# ProDoc_ESP32_V2_Interface_Board_Abed_202.net
KiCad netlist of a schematic drawn in EasyEDA Pro
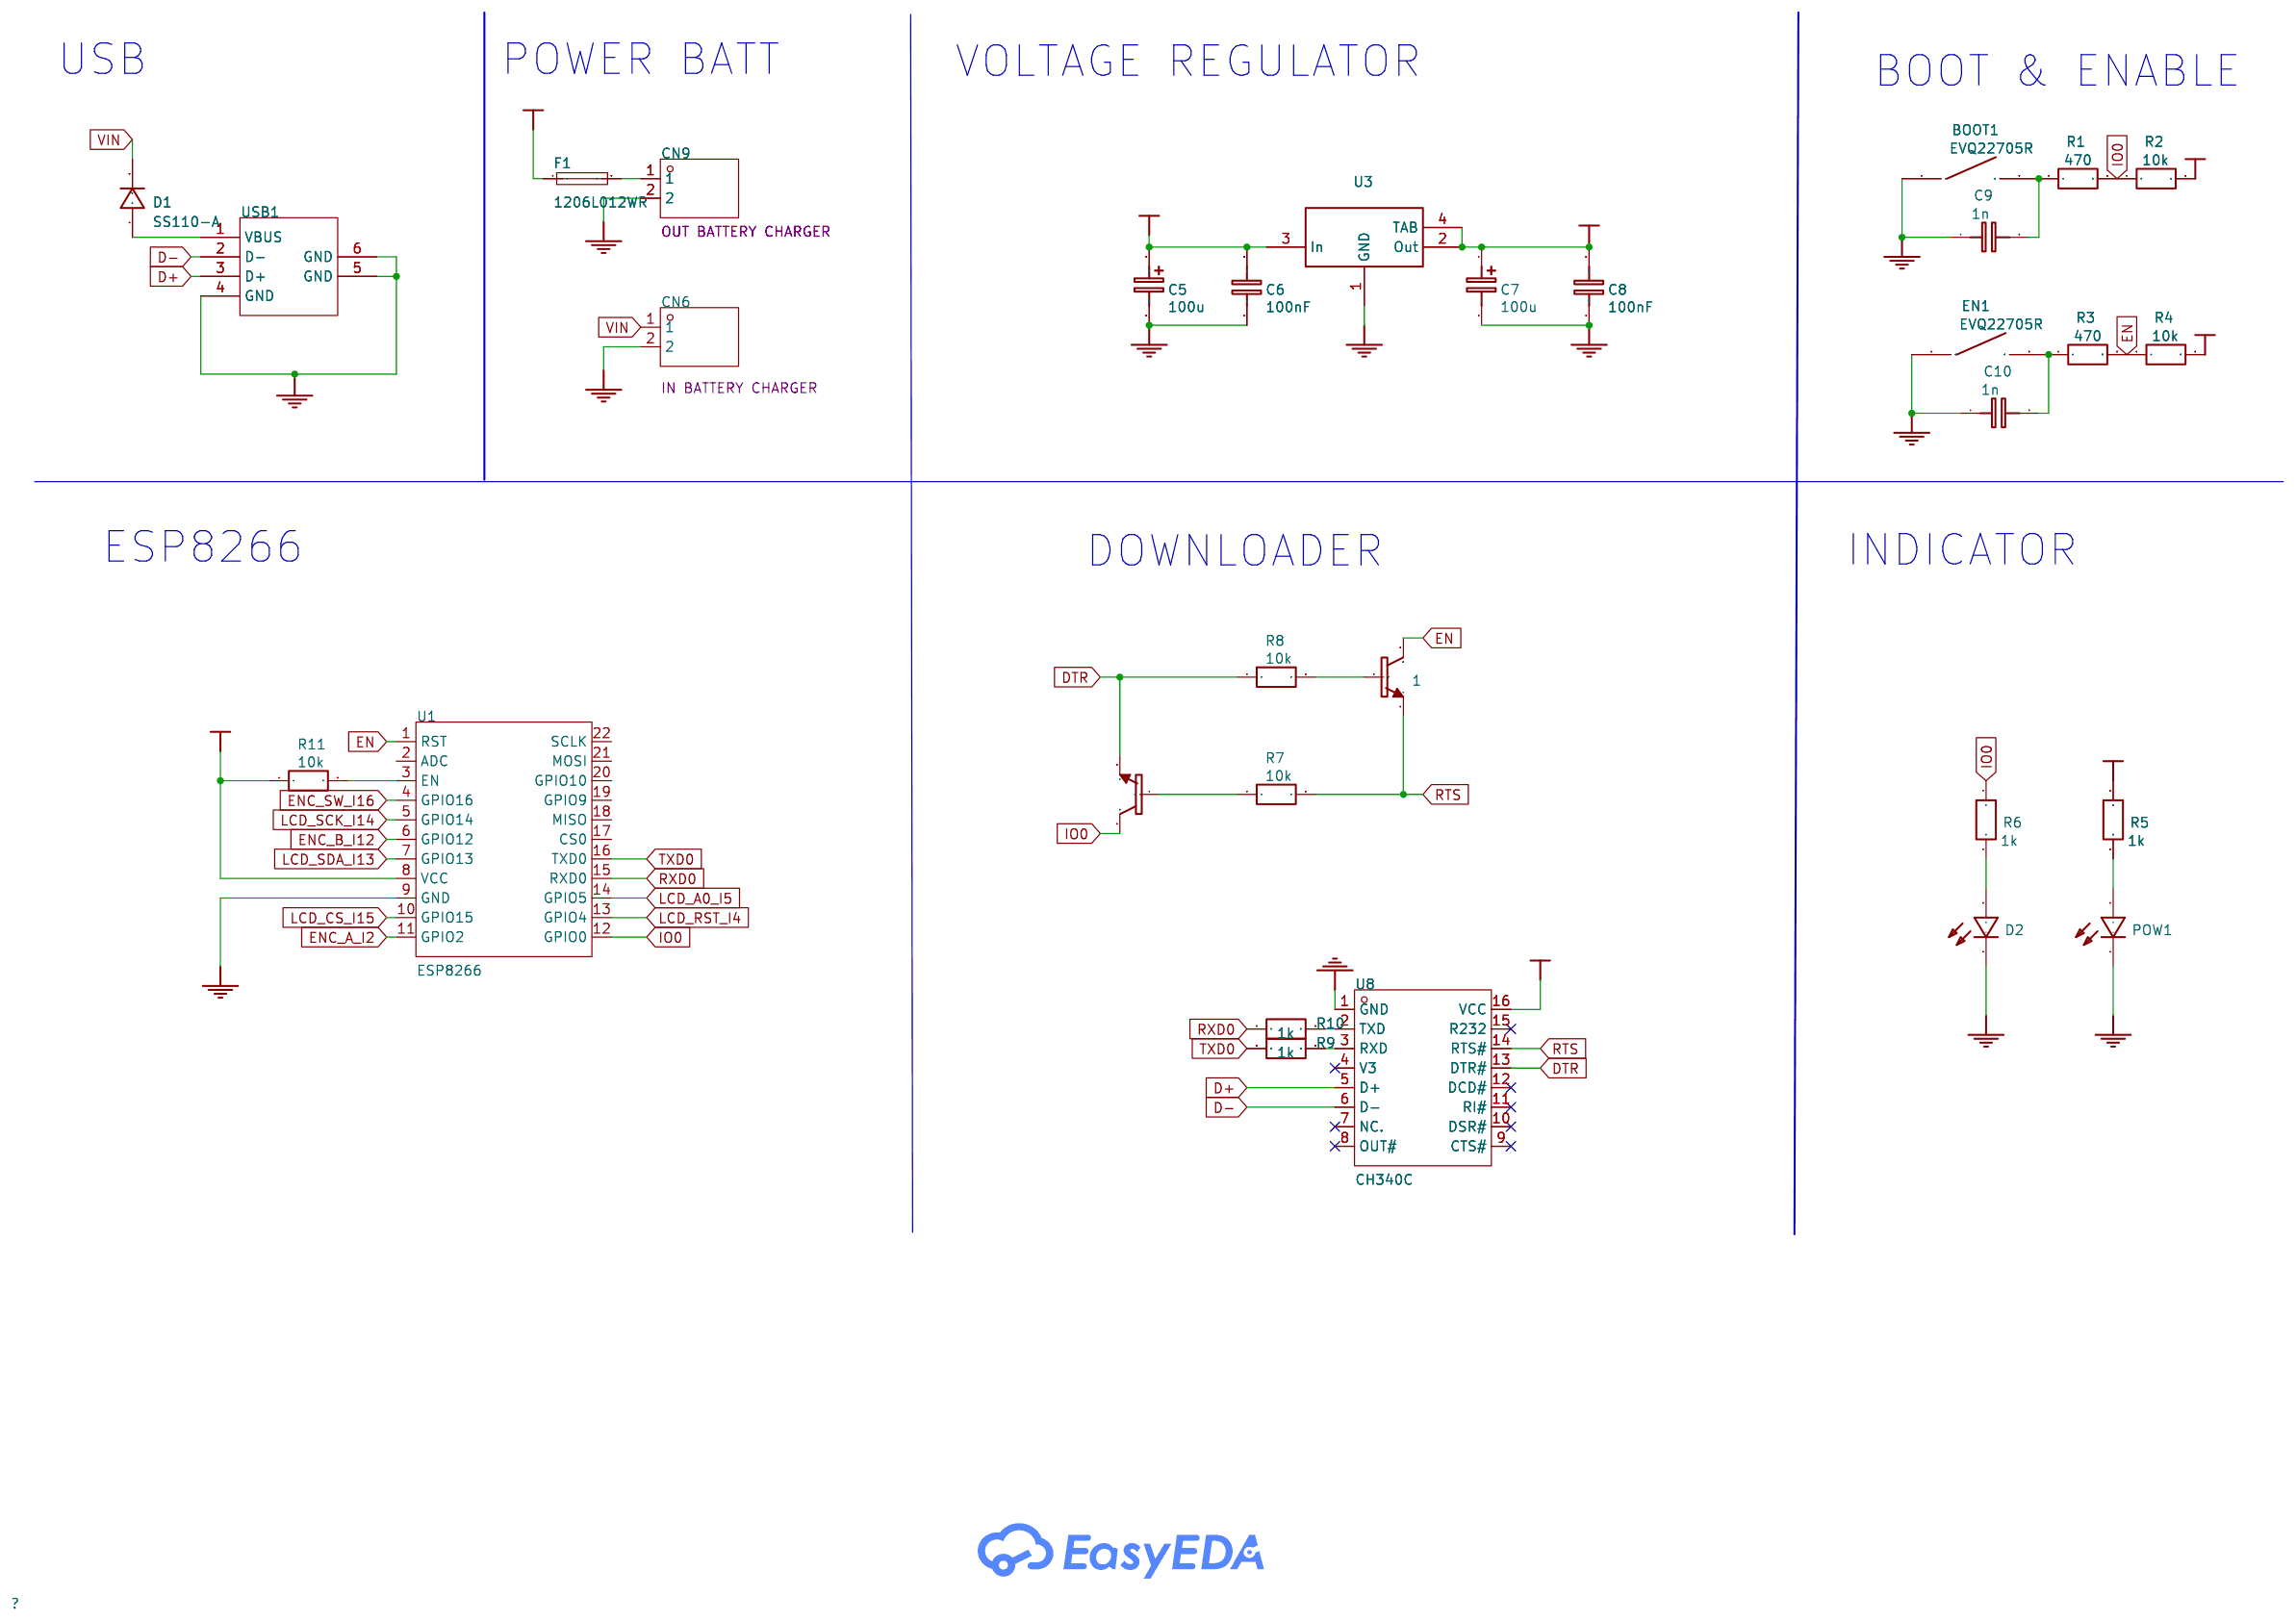
[diagram p0: Minsys]
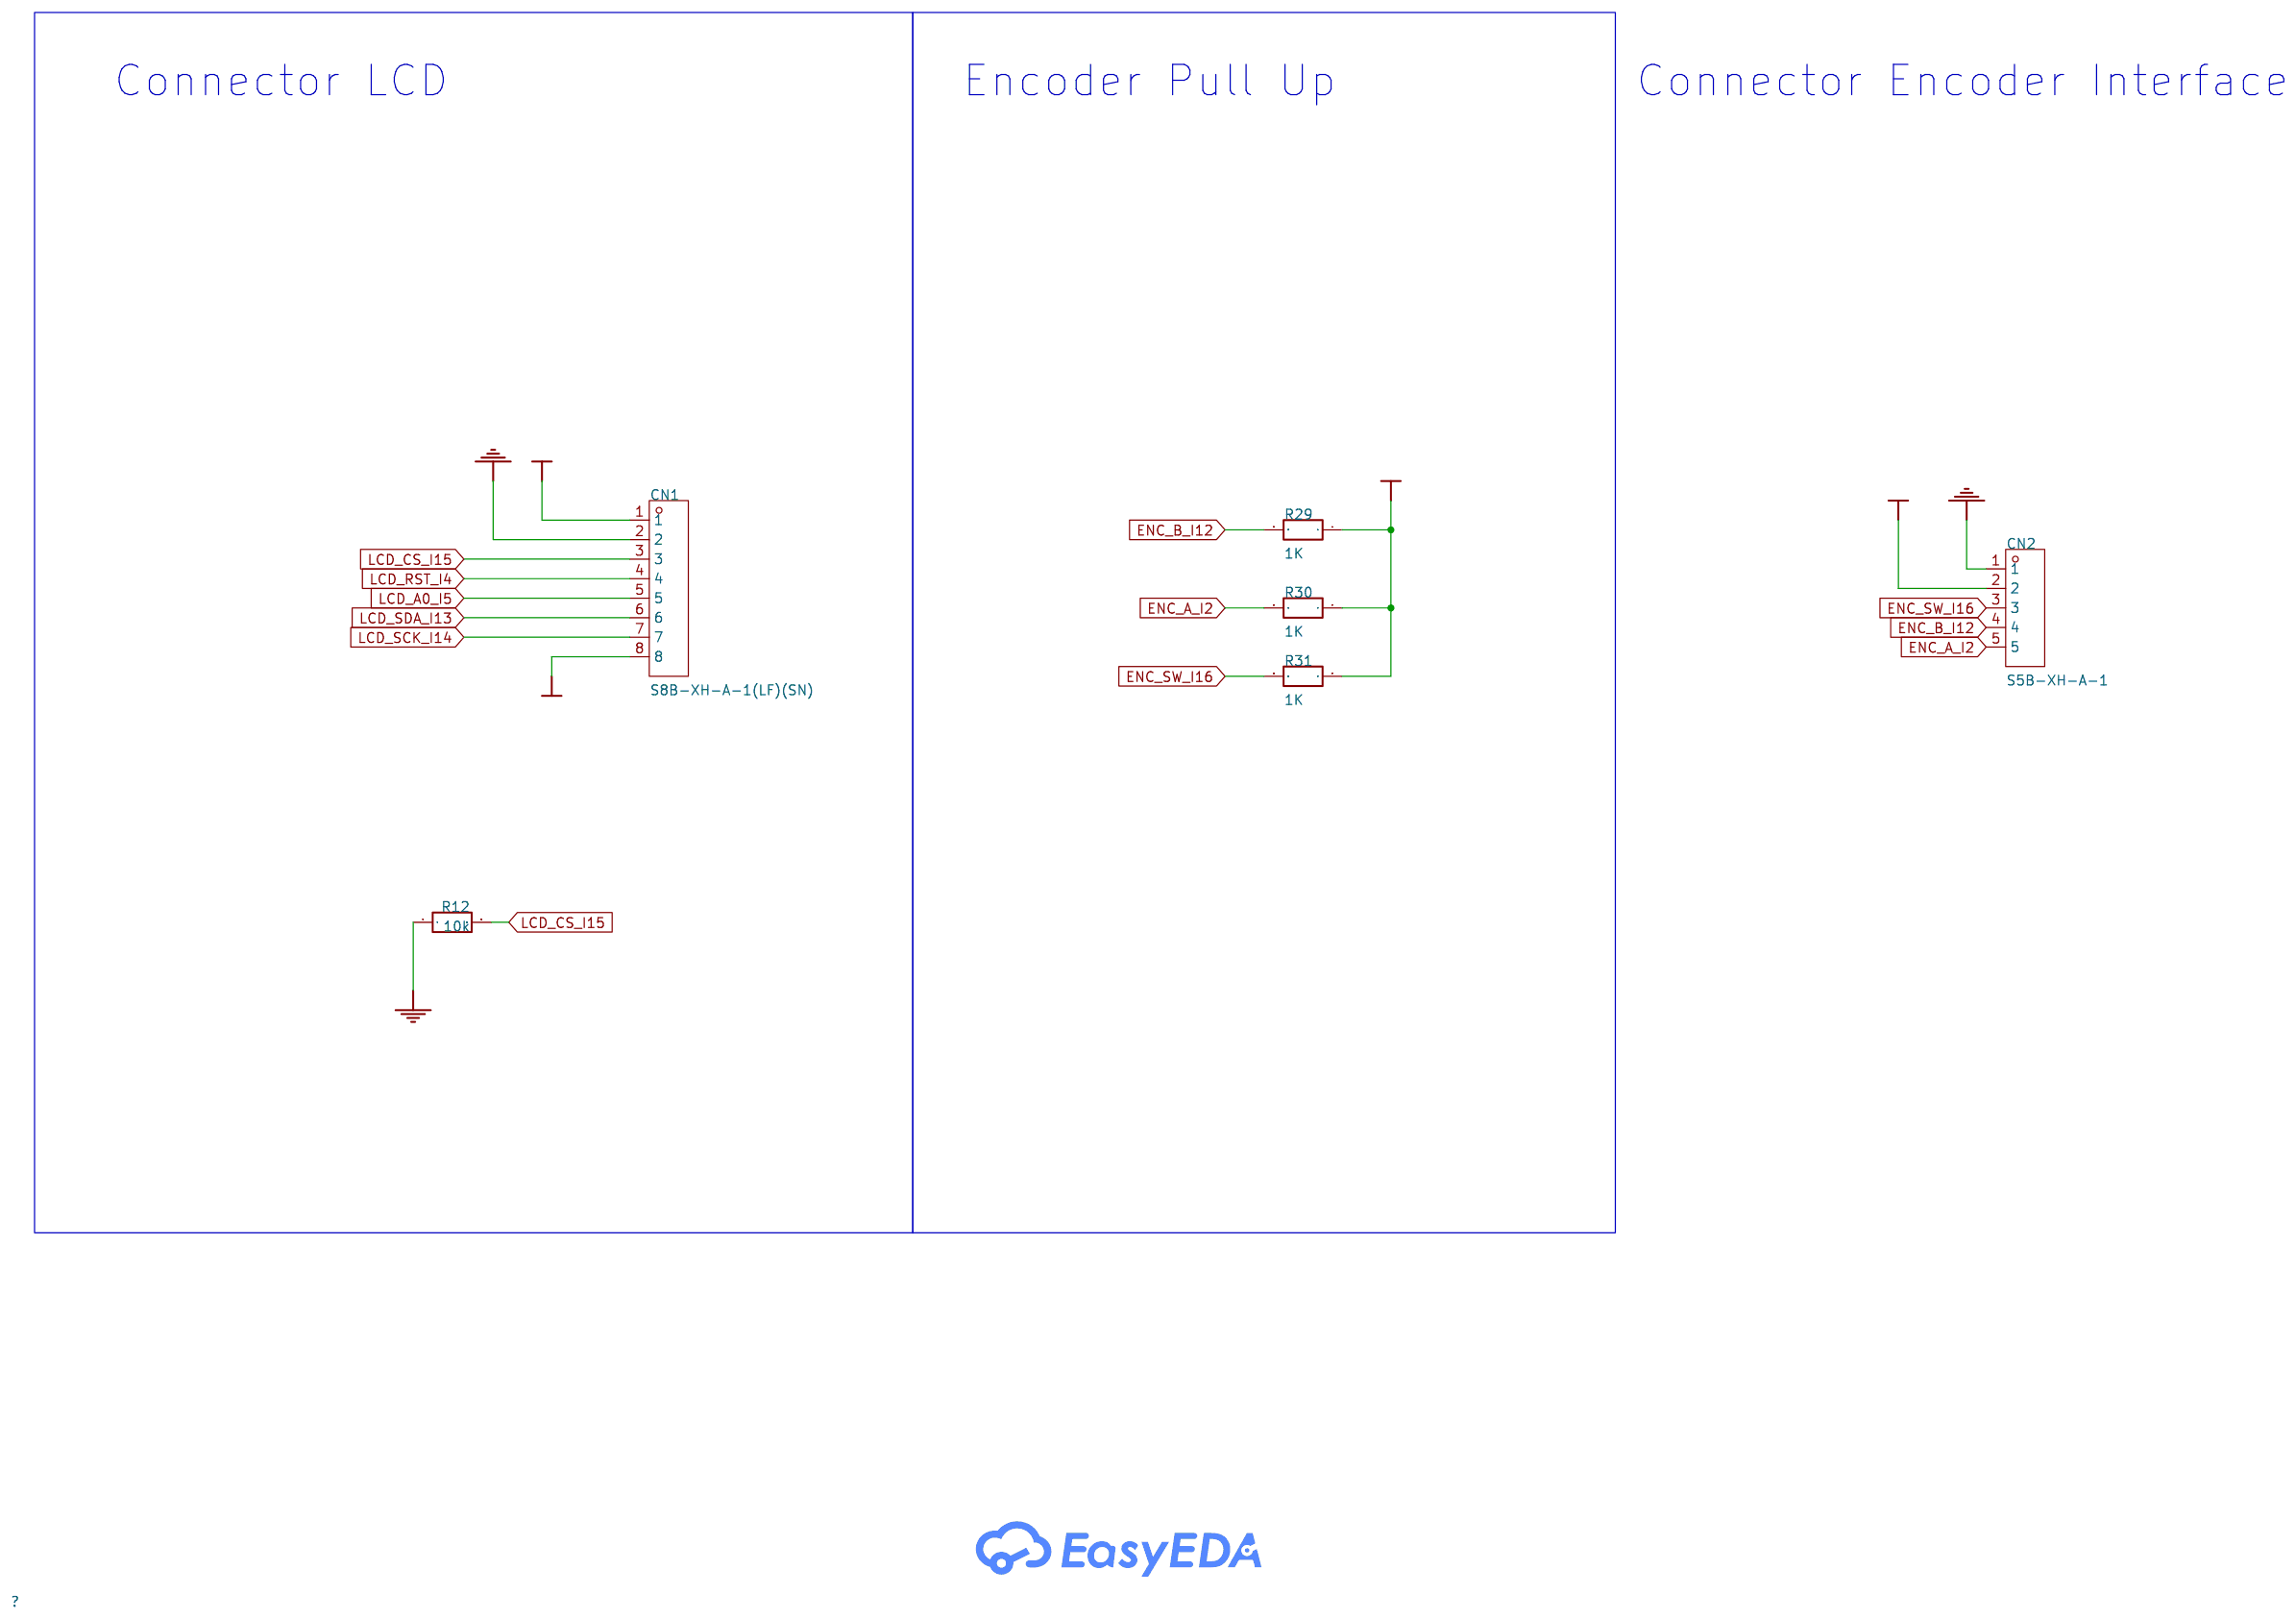
[diagram p1: INTERFACE]

(export (version "E")
  (design (tool "Eeschema 10.0.6"))
  (components
    (comp (ref "1")
      (value "MMBT3904")
      (fields (field (name "Manufacturer") "LJ(朗捷)"))
      (libsource (lib "") (part "J3Y_NPN_1"))
    )
    (comp (ref "2")
      (value "MMBT3904")
      (fields (field (name "Manufacturer") "LJ(朗捷)"))
      (libsource (lib "easyedapro") (part "J3Y_NPN"))
    )
    (comp (ref "BOOT1")
      (value "EVQ22705R")
      (footprint "easyedapro:SMD_PUSH")
      (fields (field (name "Manufacturer") "PANASONIC") (field (name "Contributor") "LCSC"))
      (libsource (lib "easyedapro") (part "EVQ22705R"))
    )
    (comp (ref "C5")
      (value "100u")
      (footprint "easyedapro:CASE-A_3216")
      (fields (field (name "Contributor") "LCEDA_Lib"))
      (libsource (lib "easyedapro") (part "100u"))
    )
    (comp (ref "C6")
      (value "100nF")
      (footprint "easyedapro:C0603")
      (fields (field (name "Contributor") "LCEDA_Lib"))
      (libsource (lib "easyedapro") (part "100nF"))
    )
    (comp (ref "C7")
      (value "100u")
      (footprint "easyedapro:CASE-A_3216")
      (fields (field (name "Contributor") "LCEDA_Lib"))
      (libsource (lib "easyedapro") (part "100u"))
    )
    (comp (ref "C8")
      (value "100nF")
      (footprint "easyedapro:C0603")
      (fields (field (name "Contributor") "LCEDA_Lib"))
      (libsource (lib "easyedapro") (part "100nF"))
    )
    (comp (ref "C9") (value "1n") (footprint "easyedapro:C0603") (libsource (lib "easyedapro") (part "1n")))
    (comp (ref "C10") (value "1n") (footprint "easyedapro:C0603") (libsource (lib "easyedapro") (part "1n")))
    (comp (ref "CN6")
      (value "S2B-XH-A-1(LF)(SN)")
      (footprint "easyedapro:CONN-TH_S2B-XH-A-1-LF-SN")
      (description "IN BATTERY CHARGER")
      (fields (field (name "Manufacturer") "JST"))
      (libsource (lib "easyedapro") (part "S2B-XH-A-1 (LF)(SN)"))
    )
    (comp (ref "CN9")
      (value "S2B-XH-A-1(LF)(SN)")
      (footprint "easyedapro:CONN-TH_S2B-XH-A-1-LF-SN")
      (description "OUT BATTERY CHARGER")
      (fields (field (name "Manufacturer") "JST"))
      (libsource (lib "easyedapro") (part "S2B-XH-A-1 (LF)(SN)"))
    )
    (comp (ref "D1")
      (value "SS110-A")
      (footprint "easyedapro:D0805")
      (fields (field (name "Manufacturer") "FMS") (field (name "Contributor") "LCSC"))
      (libsource (lib "easyedapro") (part "SS110-A"))
    )
    (comp (ref "D2")
      (value "17-21/BHC-XL2M2TY/3T")
      (footprint "easyedapro:LED0805-R-RD_BLUE")
      (fields (field (name "Manufacturer") "EVERLIGHT"))
      (libsource (lib "easyedapro") (part "17-21/BHC-XL2M2TY/3T"))
    )
    (comp (ref "EN1")
      (value "EVQ22705R")
      (footprint "easyedapro:SMD_PUSH")
      (fields (field (name "Manufacturer") "PANASONIC") (field (name "Contributor") "LCSC"))
      (libsource (lib "easyedapro") (part "EVQ22705R"))
    )
    (comp (ref "F1")
      (value "1206L012WR")
      (footprint "easyedapro:F1206")
      (fields (field (name "Manufacturer") "Littelfuse(美国力特)"))
      (libsource (lib "easyedapro") (part "1206L012WR"))
    )
    (comp (ref "POW1")
      (value "17-21/BHC-XL2M2TY/3T")
      (footprint "easyedapro:LED0805-R-RD_BLUE")
      (fields (field (name "Manufacturer") "EVERLIGHT"))
      (libsource (lib "easyedapro") (part "17-21/BHC-XL2M2TY/3T"))
    )
    (comp (ref "R1") (value "470") (footprint "easyedapro:R0603") (libsource (lib "easyedapro") (part "470")))
    (comp (ref "R2") (value "10k") (footprint "easyedapro:R0603") (libsource (lib "easyedapro") (part "10k")))
    (comp (ref "R3") (value "470") (footprint "easyedapro:R0603") (libsource (lib "easyedapro") (part "470")))
    (comp (ref "R4") (value "10k") (footprint "easyedapro:R0603") (libsource (lib "easyedapro") (part "10k")))
    (comp (ref "R5") (value "1k") (footprint "easyedapro:R0603") (libsource (lib "easyedapro") (part "1k")))
    (comp (ref "R6") (value "1k") (footprint "easyedapro:R0603") (libsource (lib "easyedapro") (part "1k")))
    (comp (ref "R7") (value "10k") (footprint "easyedapro:R0603") (libsource (lib "easyedapro") (part "10k")))
    (comp (ref "R8") (value "10k") (footprint "easyedapro:R0603") (libsource (lib "easyedapro") (part "10k")))
    (comp (ref "R9")
      (value "1k")
      (footprint "easyedapro:R0603")
      (fields (field (name "Contributor") "LCEDA_Lib"))
      (libsource (lib "") (part "1k_1"))
    )
    (comp (ref "R10")
      (value "1k")
      (footprint "easyedapro:R0603")
      (fields (field (name "Contributor") "LCEDA_Lib"))
      (libsource (lib "") (part "1k_1"))
    )
    (comp (ref "R11")
      (value "10k")
      (footprint "easyedapro:R0603")
      (libsource (lib "easyedapro") (part "10k"))
    )
    (comp (ref "U1")
      (value "ESP8266")
      (footprint "easyedapro:WIFIM-SMD_ESP-12F-ESP8266MOD")
      (libsource (lib "easyedapro") (part "ESP8266"))
    )
    (comp (ref "U3") (value "AMS1117-3.3") (libsource (lib "easyedapro") (part "AMS1117-3.3")))
    (comp (ref "U8")
      (value "CH340C")
      (footprint "easyedapro:SOP-16_L10.0-W3.9-P1.27-LS6.0-BL")
      (fields (field (name "Manufacturer") "WCH(南京沁恒)"))
      (libsource (lib "easyedapro") (part "CH340C"))
    )
    (comp (ref "USB1")
      (value "USB-B01")
      (footprint "easyedapro:USB-B-TH_USB-B01")
      (fields (field (name "Manufacturer") "SOFNG(硕方)"))
      (libsource (lib "easyedapro") (part "USB-B01"))
    )
    (comp (ref "CN1")
      (value "S8B-XH-A-1(LF)(SN)")
      (footprint "easyedapro:CONN-TH_S8B-XH-A-1-LF-SN")
      (fields (field (name "Manufacturer") "JST"))
      (libsource (lib "easyedapro") (part "S8B-XH-A-1(LF)(SN)_C5306549"))
    )
    (comp (ref "CN2")
      (value "S5B-XH-A-1")
      (footprint "easyedapro:CONN-TH_S5B-XH-A-1-LF-SN")
      (fields (field (name "Manufacturer") "JST"))
      (libsource (lib "easyedapro") (part "S5B-XH-A-1"))
    )
    (comp (ref "R12")
      (value "10k")
      (footprint "easyedapro:R0603")
      (libsource (lib "easyedapro") (part "10k"))
    )
    (comp (ref "R29") (value "1K") (footprint "easyedapro:R0603") (libsource (lib "easyedapro") (part "10k")))
    (comp (ref "R30") (value "1K") (footprint "easyedapro:R0603") (libsource (lib "easyedapro") (part "10k")))
    (comp (ref "R31") (value "1K") (footprint "easyedapro:R0603") (libsource (lib "easyedapro") (part "10k")))
  )
  (nets
    (net (code "1") (name "+5V") (class "Default")
      (node (ref "C5") (pin "1") (pinfunction "1_1") (pintype "unspecified"))
      (node (ref "C6") (pin "2") (pinfunction "2_2") (pintype "unspecified"))
      (node (ref "CN1") (pin "8") (pinfunction "8_8") (pintype "unspecified"))
      (node (ref "F1") (pin "1") (pinfunction "1_1") (pintype "input"))
      (node (ref "U3") (pin "3") (pinfunction "In_3") (pintype "unspecified"))
      (node (ref "U8") (pin "16") (pinfunction "VCC_16") (pintype "unspecified"))
    )
    (net (code "2") (name "3V3") (class "Default")
      (node (ref "C7") (pin "1") (pinfunction "1_1") (pintype "unspecified"))
      (node (ref "C8") (pin "2") (pinfunction "2_2") (pintype "unspecified"))
      (node (ref "CN1") (pin "1") (pinfunction "1_1") (pintype "unspecified"))
      (node (ref "CN2") (pin "2") (pinfunction "2_2") (pintype "unspecified"))
      (node (ref "R11") (pin "1") (pinfunction "1_1") (pintype "unspecified"))
      (node (ref "R2") (pin "2") (pinfunction "2_2") (pintype "unspecified"))
      (node (ref "R29") (pin "1") (pinfunction "1_1") (pintype "unspecified"))
      (node (ref "R30") (pin "1") (pinfunction "1_1") (pintype "unspecified"))
      (node (ref "R31") (pin "1") (pinfunction "1_1") (pintype "unspecified"))
      (node (ref "R4") (pin "2") (pinfunction "2_2") (pintype "unspecified"))
      (node (ref "R5") (pin "1") (pinfunction "1_1") (pintype "unspecified"))
      (node (ref "U1") (pin "8") (pinfunction "VCC_8") (pintype "unspecified"))
      (node (ref "U3") (pin "2") (pinfunction "Out_2") (pintype "unspecified"))
      (node (ref "U3") (pin "4") (pinfunction "TAB_4") (pintype "unspecified"))
    )
    (net (code "3") (name "D+") (class "Default")
      (node (ref "U8") (pin "5") (pinfunction "D+_5") (pintype "unspecified"))
      (node (ref "USB1") (pin "3") (pinfunction "D+_3") (pintype "unspecified"))
    )
    (net (code "4") (name "D-") (class "Default")
      (node (ref "U8") (pin "6") (pinfunction "D-_6") (pintype "unspecified"))
      (node (ref "USB1") (pin "2") (pinfunction "D-_2") (pintype "unspecified"))
    )
    (net (code "5") (name "DTR") (class "Default")
      (node (ref "2") (pin "3") (pinfunction "E_3") (pintype "bidirectional"))
      (node (ref "R8") (pin "1") (pinfunction "1_1") (pintype "unspecified"))
      (node (ref "U8") (pin "13") (pinfunction "DTR#_13") (pintype "unspecified"))
    )
    (net (code "6") (name "EN") (class "Default")
      (node (ref "1") (pin "2") (pinfunction "C_2") (pintype "bidirectional"))
      (node (ref "R3") (pin "2") (pinfunction "2_2") (pintype "unspecified"))
      (node (ref "R4") (pin "1") (pinfunction "1_1") (pintype "unspecified"))
      (node (ref "U1") (pin "1") (pinfunction "RST_1") (pintype "unspecified"))
    )
    (net (code "7") (name "ENC_A_I2") (class "Default")
      (node (ref "CN2") (pin "5") (pinfunction "5_5") (pintype "unspecified"))
      (node (ref "R30") (pin "2") (pinfunction "2_2") (pintype "unspecified"))
      (node (ref "U1") (pin "11") (pinfunction "GPIO2_11") (pintype "unspecified"))
    )
    (net (code "8") (name "ENC_B_I12") (class "Default")
      (node (ref "CN2") (pin "4") (pinfunction "4_4") (pintype "unspecified"))
      (node (ref "R29") (pin "2") (pinfunction "2_2") (pintype "unspecified"))
      (node (ref "U1") (pin "6") (pinfunction "GPIO12_6") (pintype "unspecified"))
    )
    (net (code "9") (name "ENC_SW_I16") (class "Default")
      (node (ref "CN2") (pin "3") (pinfunction "3_3") (pintype "unspecified"))
      (node (ref "R31") (pin "2") (pinfunction "2_2") (pintype "unspecified"))
      (node (ref "U1") (pin "4") (pinfunction "GPIO16_4") (pintype "unspecified"))
    )
    (net (code "10") (name "GND") (class "Default")
      (node (ref "BOOT1") (pin "1") (pinfunction "1_1") (pintype "input"))
      (node (ref "C10") (pin "1") (pinfunction "1_1") (pintype "unspecified"))
      (node (ref "C5") (pin "2") (pinfunction "2_2") (pintype "unspecified"))
      (node (ref "C6") (pin "1") (pinfunction "1_1") (pintype "unspecified"))
      (node (ref "C7") (pin "2") (pinfunction "2_2") (pintype "unspecified"))
      (node (ref "C8") (pin "1") (pinfunction "1_1") (pintype "unspecified"))
      (node (ref "C9") (pin "1") (pinfunction "1_1") (pintype "unspecified"))
      (node (ref "CN1") (pin "2") (pinfunction "2_2") (pintype "unspecified"))
      (node (ref "CN2") (pin "1") (pinfunction "1_1") (pintype "unspecified"))
      (node (ref "CN6") (pin "2") (pinfunction "2_2") (pintype "unspecified"))
      (node (ref "CN9") (pin "2") (pinfunction "2_2") (pintype "unspecified"))
      (node (ref "D2") (pin "1") (pinfunction "-_1") (pintype "input"))
      (node (ref "EN1") (pin "1") (pinfunction "1_1") (pintype "input"))
      (node (ref "POW1") (pin "1") (pinfunction "-_1") (pintype "input"))
      (node (ref "R12") (pin "1") (pinfunction "1_1") (pintype "unspecified"))
      (node (ref "U1") (pin "9") (pinfunction "GND_9") (pintype "unspecified"))
      (node (ref "U3") (pin "1") (pinfunction "GND_1") (pintype "unspecified"))
      (node (ref "U8") (pin "1") (pinfunction "GND_1") (pintype "unspecified"))
      (node (ref "USB1") (pin "4") (pinfunction "GND_4") (pintype "unspecified"))
      (node (ref "USB1") (pin "5") (pinfunction "GND_5") (pintype "unspecified"))
      (node (ref "USB1") (pin "6") (pinfunction "GND_6") (pintype "unspecified"))
    )
    (net (code "11") (name "IO0") (class "Default")
      (node (ref "2") (pin "2") (pinfunction "C_2") (pintype "bidirectional"))
      (node (ref "R1") (pin "2") (pinfunction "2_2") (pintype "unspecified"))
      (node (ref "R2") (pin "1") (pinfunction "1_1") (pintype "unspecified"))
      (node (ref "R6") (pin "1") (pinfunction "1_1") (pintype "unspecified"))
      (node (ref "U1") (pin "12") (pinfunction "GPIO0_12") (pintype "unspecified"))
    )
    (net (code "12") (name "LCD_A0_I5") (class "Default")
      (node (ref "CN1") (pin "5") (pinfunction "5_5") (pintype "unspecified"))
      (node (ref "U1") (pin "14") (pinfunction "GPIO5_14") (pintype "unspecified"))
    )
    (net (code "13") (name "LCD_CS_I15") (class "Default")
      (node (ref "CN1") (pin "3") (pinfunction "3_3") (pintype "unspecified"))
      (node (ref "R12") (pin "2") (pinfunction "2_2") (pintype "unspecified"))
      (node (ref "U1") (pin "10") (pinfunction "GPIO15_10") (pintype "unspecified"))
    )
    (net (code "14") (name "LCD_RST_I4") (class "Default")
      (node (ref "CN1") (pin "4") (pinfunction "4_4") (pintype "unspecified"))
      (node (ref "U1") (pin "13") (pinfunction "GPIO4_13") (pintype "unspecified"))
    )
    (net (code "15") (name "LCD_SCK_I14") (class "Default")
      (node (ref "CN1") (pin "7") (pinfunction "7_7") (pintype "unspecified"))
      (node (ref "U1") (pin "5") (pinfunction "GPIO14_5") (pintype "unspecified"))
    )
    (net (code "16") (name "LCD_SDA_I13") (class "Default")
      (node (ref "CN1") (pin "6") (pinfunction "6_6") (pintype "unspecified"))
      (node (ref "U1") (pin "7") (pinfunction "GPIO13_7") (pintype "unspecified"))
    )
    (net (code "17") (name "Net-(1-B)") (class "Default")
      (node (ref "1") (pin "1") (pinfunction "B_1") (pintype "bidirectional"))
      (node (ref "R8") (pin "2") (pinfunction "2_2") (pintype "unspecified"))
    )
    (net (code "18") (name "Net-(2-B)") (class "Default")
      (node (ref "2") (pin "1") (pinfunction "B_1") (pintype "bidirectional"))
      (node (ref "R7") (pin "1") (pinfunction "1_1") (pintype "unspecified"))
    )
    (net (code "19") (name "Net-(BOOT1-Pad2)") (class "Default")
      (node (ref "BOOT1") (pin "2") (pinfunction "2_2") (pintype "input"))
      (node (ref "C9") (pin "2") (pinfunction "2_2") (pintype "unspecified"))
      (node (ref "R1") (pin "1") (pinfunction "1_1") (pintype "unspecified"))
    )
    (net (code "20") (name "Net-(C10-Pad2)") (class "Default")
      (node (ref "C10") (pin "2") (pinfunction "2_2") (pintype "unspecified"))
      (node (ref "EN1") (pin "2") (pinfunction "2_2") (pintype "input"))
      (node (ref "R3") (pin "1") (pinfunction "1_1") (pintype "unspecified"))
    )
    (net (code "21") (name "Net-(CN9-Pad1)") (class "Default")
      (node (ref "CN9") (pin "1") (pinfunction "1_1") (pintype "unspecified"))
      (node (ref "F1") (pin "2") (pinfunction "2_2") (pintype "input"))
    )
    (net (code "22") (name "Net-(D2-+)") (class "Default")
      (node (ref "D2") (pin "2") (pinfunction "+_2") (pintype "input"))
      (node (ref "R6") (pin "2") (pinfunction "2_2") (pintype "unspecified"))
    )
    (net (code "23") (name "Net-(POW1-+)") (class "Default")
      (node (ref "POW1") (pin "2") (pinfunction "+_2") (pintype "input"))
      (node (ref "R5") (pin "2") (pinfunction "2_2") (pintype "unspecified"))
    )
    (net (code "24") (name "Net-(U1-EN)") (class "Default")
      (node (ref "R11") (pin "2") (pinfunction "2_2") (pintype "unspecified"))
      (node (ref "U1") (pin "3") (pinfunction "EN_3") (pintype "unspecified"))
    )
    (net (code "25") (name "Net-(U8-RXD)") (class "Default")
      (node (ref "R9") (pin "2") (pinfunction "2_2") (pintype "unspecified"))
      (node (ref "U8") (pin "3") (pinfunction "RXD_3") (pintype "unspecified"))
    )
    (net (code "26") (name "Net-(U8-TXD)") (class "Default")
      (node (ref "R10") (pin "2") (pinfunction "2_2") (pintype "unspecified"))
      (node (ref "U8") (pin "2") (pinfunction "TXD_2") (pintype "unspecified"))
    )
    (net (code "27") (name "Net-(USB1-VBUS)") (class "Default")
      (node (ref "D1") (pin "1") (pinfunction "1_1") (pintype "unspecified"))
      (node (ref "USB1") (pin "1") (pinfunction "VBUS_1") (pintype "unspecified"))
    )
    (net (code "28") (name "RTS") (class "Default")
      (node (ref "1") (pin "3") (pinfunction "E_3") (pintype "bidirectional"))
      (node (ref "R7") (pin "2") (pinfunction "2_2") (pintype "unspecified"))
      (node (ref "U8") (pin "14") (pinfunction "RTS#_14") (pintype "unspecified"))
    )
    (net (code "29") (name "RXD0") (class "Default")
      (node (ref "R10") (pin "1") (pinfunction "1_1") (pintype "unspecified"))
      (node (ref "U1") (pin "15") (pinfunction "RXD0_15") (pintype "unspecified"))
    )
    (net (code "30") (name "TXD0") (class "Default")
      (node (ref "R9") (pin "1") (pinfunction "1_1") (pintype "unspecified"))
      (node (ref "U1") (pin "16") (pinfunction "TXD0_16") (pintype "unspecified"))
    )
    (net (code "31") (name "VIN") (class "Default")
      (node (ref "CN6") (pin "1") (pinfunction "1_1") (pintype "unspecified"))
      (node (ref "D1") (pin "2") (pinfunction "2_2") (pintype "unspecified"))
    )
    (net (code "32") (name "unconnected-(U1-ADC-Pad2)") (class "Default")
      (node (ref "U1") (pin "2") (pinfunction "ADC_2") (pintype "unspecified"))
    )
    (net (code "33") (name "unconnected-(U1-CS0-Pad17)") (class "Default")
      (node (ref "U1") (pin "17") (pinfunction "CS0_17") (pintype "unspecified"))
    )
    (net (code "34") (name "unconnected-(U1-GPIO9-Pad19)") (class "Default")
      (node (ref "U1") (pin "19") (pinfunction "GPIO9_19") (pintype "unspecified"))
    )
    (net (code "35") (name "unconnected-(U1-GPIO10-Pad20)") (class "Default")
      (node (ref "U1") (pin "20") (pinfunction "GPIO10_20") (pintype "unspecified"))
    )
    (net (code "36") (name "unconnected-(U1-MISO-Pad18)") (class "Default")
      (node (ref "U1") (pin "18") (pinfunction "MISO_18") (pintype "unspecified"))
    )
    (net (code "37") (name "unconnected-(U1-MOSI-Pad21)") (class "Default")
      (node (ref "U1") (pin "21") (pinfunction "MOSI_21") (pintype "unspecified"))
    )
    (net (code "38") (name "unconnected-(U1-SCLK-Pad22)") (class "Default")
      (node (ref "U1") (pin "22") (pinfunction "SCLK_22") (pintype "unspecified"))
    )
    (net (code "39") (name "unconnected-(U8-CTS#-Pad9)") (class "Default")
      (node (ref "U8") (pin "9") (pinfunction "CTS#_9") (pintype "unspecified+no_connect"))
    )
    (net (code "40") (name "unconnected-(U8-DCD#-Pad12)") (class "Default")
      (node (ref "U8") (pin "12") (pinfunction "DCD#_12") (pintype "unspecified+no_connect"))
    )
    (net (code "41") (name "unconnected-(U8-DSR#-Pad10)") (class "Default")
      (node (ref "U8") (pin "10") (pinfunction "DSR#_10") (pintype "unspecified+no_connect"))
    )
    (net (code "42") (name "unconnected-(U8-NC.-Pad7)") (class "Default")
      (node (ref "U8") (pin "7") (pinfunction "NC._7") (pintype "unspecified+no_connect"))
    )
    (net (code "43") (name "unconnected-(U8-OUT#-Pad8)") (class "Default")
      (node (ref "U8") (pin "8") (pinfunction "OUT#_8") (pintype "unspecified+no_connect"))
    )
    (net (code "44") (name "unconnected-(U8-R232-Pad15)") (class "Default")
      (node (ref "U8") (pin "15") (pinfunction "R232_15") (pintype "unspecified+no_connect"))
    )
    (net (code "45") (name "unconnected-(U8-RI#-Pad11)") (class "Default")
      (node (ref "U8") (pin "11") (pinfunction "RI#_11") (pintype "unspecified+no_connect"))
    )
    (net (code "46") (name "unconnected-(U8-V3-Pad4)") (class "Default")
      (node (ref "U8") (pin "4") (pinfunction "V3_4") (pintype "unspecified+no_connect"))
    )
  )
)
